# SCB_vongcochopet.net
KiCad netlist of a schematic drawn in Altium Designer
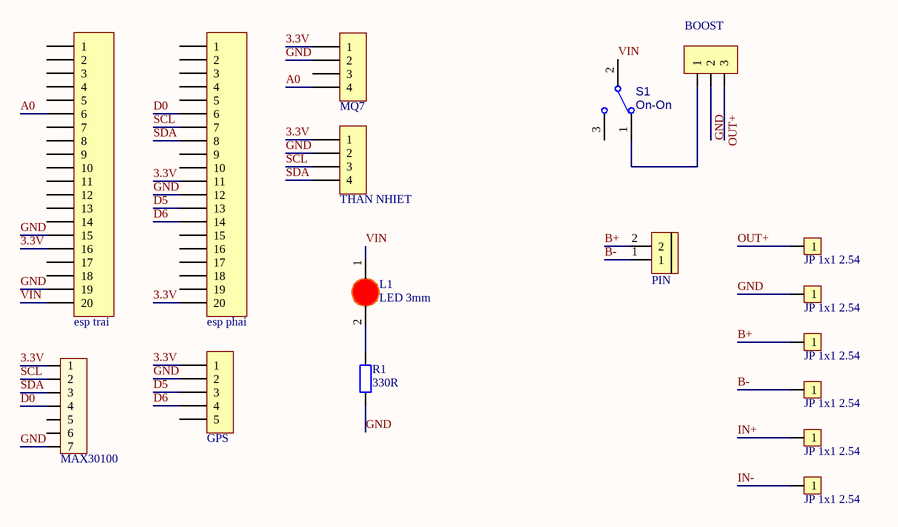
[diagram p0: SCB_vongcochopet.schdoc]

(export (version "E")
  (design (tool "Eeschema 10.0.6"))
  (components
    (comp (ref "H1")
      (value "MQ7")
      (footprint "Header DT 4P_2.54")
      (description "Cắm")
      (libsource (lib "Altium_Lib_by_KhueNguyenCreator") (part "Header 4P 2.54 Duc Thang"))
    )
    (comp (ref "H2")
      (value "THAN NHIET")
      (footprint "Header DT 4P_2.54")
      (description "Cắm")
      (libsource (lib "Altium_Lib_by_KhueNguyenCreator") (part "Header 4P 2.54 Duc Thang"))
    )
    (comp (ref "H3")
      (value "GPS")
      (footprint "Header DT 5P_2.54")
      (description "Cắm")
      (libsource (lib "Altium_Lib_by_KhueNguyenCreator") (part "Header 5P 2.54 Duc Thang"))
    )
    (comp (ref "H4")
      (value "MAX30100")
      (footprint "Header DT 7P_2.54")
      (description "Cắm")
      (libsource (lib "Altium_Lib_by_KhueNguyenCreator") (part "Header 7P 2.54 Duc Thang"))
    )
    (comp (ref "JP1")
      (value "esp trai")
      (footprint "JP 1x20 CT")
      (description "Cắm")
      (libsource (lib "Altium_Lib_by_KhueNguyenCreator") (part "JP 1x20 2.54 Cai Thang"))
    )
    (comp (ref "JP2")
      (value "esp phai")
      (footprint "JP 1x20 CT")
      (description "Cắm")
      (libsource (lib "Altium_Lib_by_KhueNguyenCreator") (part "JP 1x20 2.54 Cai Thang"))
    )
    (comp (ref "JP3")
      (value "BOOST")
      (footprint "JP 1x3 DT")
      (description "Cắm")
      (libsource (lib "Altium_Lib_by_KhueNguyenCreator") (part "JP 1x3 2.54 Duc Thang"))
    )
    (comp (ref "JP4")
      (value "JP 1x1 2.54")
      (footprint "JP 1x1 DT")
      (description "Cắm")
      (libsource (lib "Altium_Lib_by_KhueNguyenCreator") (part "JP 1x1 2.54 Duc Thang"))
    )
    (comp (ref "JP5")
      (value "JP 1x1 2.54")
      (footprint "JP 1x1 DT")
      (description "Cắm")
      (libsource (lib "Altium_Lib_by_KhueNguyenCreator") (part "JP 1x1 2.54 Duc Thang"))
    )
    (comp (ref "JP6")
      (value "JP 1x1 2.54")
      (footprint "JP 1x1 DT")
      (description "Cắm")
      (libsource (lib "Altium_Lib_by_KhueNguyenCreator") (part "JP 1x1 2.54 Duc Thang"))
    )
    (comp (ref "JP7")
      (value "JP 1x1 2.54")
      (footprint "JP 1x1 DT")
      (description "Cắm")
      (libsource (lib "Altium_Lib_by_KhueNguyenCreator") (part "JP 1x1 2.54 Duc Thang"))
    )
    (comp (ref "JP8")
      (value "JP 1x1 2.54")
      (footprint "JP 1x1 DT")
      (description "Cắm")
      (libsource (lib "Altium_Lib_by_KhueNguyenCreator") (part "JP 1x1 2.54 Duc Thang"))
    )
    (comp (ref "JP9")
      (value "JP 1x1 2.54")
      (footprint "JP 1x1 DT")
      (description "Cắm")
      (libsource (lib "Altium_Lib_by_KhueNguyenCreator") (part "JP 1x1 2.54 Duc Thang"))
    )
    (comp (ref "KF1")
      (value "PIN")
      (footprint "Con 2 KF301 5.08")
      (description "Cắm")
      (libsource (lib "Altium_Lib_by_KhueNguyenCreator") (part "CON 2 KF301"))
    )
    (comp (ref "L1")
      (value "LED 3mm")
      (footprint "LED-3MM-RED")
      (description "Cắm")
      (libsource (lib "Altium_Lib_by_KhueNguyenCreator") (part "LED 3mm Do"))
    )
    (comp (ref "R1")
      (value "330R")
      (footprint "tro vach 1/4w")
      (description "Cắm")
      (libsource (lib "Altium_Lib_by_KhueNguyenCreator") (part "Tro Vach 1/4W 5% 330R"))
    )
    (comp (ref "S1")
      (value "ON-ON")
      (footprint "SWITCH_SPDT_SLIDER")
      (description "Switch THD vertical toggle SPDT")
      (fields (field (name "SWITCH FUNCTION") "On-On"))
      (libsource (lib "My library altium") (part "SW_THD_SPDT_On-On"))
    )
  )
  (nets
    (net (code "1") (name "/3.3V") (class "Default")
      (node (ref "H1") (pin "1") (pinfunction "1_1") (pintype "passive"))
      (node (ref "H2") (pin "1") (pinfunction "1_1") (pintype "passive"))
      (node (ref "H3") (pin "1") (pinfunction "1_1") (pintype "passive"))
      (node (ref "H4") (pin "1") (pinfunction "1_1") (pintype "passive"))
      (node (ref "JP1") (pin "16") (pinfunction "16_16") (pintype "passive"))
      (node (ref "JP2") (pin "11") (pinfunction "11_11") (pintype "passive"))
      (node (ref "JP2") (pin "20") (pinfunction "20_20") (pintype "passive"))
    )
    (net (code "2") (name "/A0") (class "Default")
      (node (ref "H1") (pin "4") (pinfunction "4_4") (pintype "passive"))
      (node (ref "JP1") (pin "6") (pinfunction "6_6") (pintype "passive"))
    )
    (net (code "3") (name "/B+") (class "Default")
      (node (ref "JP6") (pin "1") (pinfunction "1_1") (pintype "passive"))
      (node (ref "KF1") (pin "2") (pinfunction "2_2") (pintype "passive"))
    )
    (net (code "4") (name "/B-") (class "Default")
      (node (ref "JP7") (pin "1") (pinfunction "1_1") (pintype "passive"))
      (node (ref "KF1") (pin "1") (pinfunction "1_1") (pintype "passive"))
    )
    (net (code "5") (name "/D0") (class "Default")
      (node (ref "H4") (pin "4") (pinfunction "4_4") (pintype "passive"))
      (node (ref "JP2") (pin "6") (pinfunction "6_6") (pintype "passive"))
    )
    (net (code "6") (name "/D5") (class "Default")
      (node (ref "H3") (pin "3") (pinfunction "3_3") (pintype "passive"))
      (node (ref "JP2") (pin "13") (pinfunction "13_13") (pintype "passive"))
    )
    (net (code "7") (name "/D6") (class "Default")
      (node (ref "H3") (pin "4") (pinfunction "4_4") (pintype "passive"))
      (node (ref "JP2") (pin "14") (pinfunction "14_14") (pintype "passive"))
    )
    (net (code "8") (name "/GND") (class "Default")
      (node (ref "H1") (pin "2") (pinfunction "2_2") (pintype "passive"))
      (node (ref "H2") (pin "2") (pinfunction "2_2") (pintype "passive"))
      (node (ref "H3") (pin "2") (pinfunction "2_2") (pintype "passive"))
      (node (ref "H4") (pin "7") (pinfunction "7_7") (pintype "passive"))
      (node (ref "JP1") (pin "15") (pinfunction "15_15") (pintype "passive"))
      (node (ref "JP1") (pin "19") (pinfunction "19_19") (pintype "passive"))
      (node (ref "JP2") (pin "12") (pinfunction "12_12") (pintype "passive"))
      (node (ref "JP3") (pin "2") (pinfunction "2_2") (pintype "passive"))
      (node (ref "JP5") (pin "1") (pinfunction "1_1") (pintype "passive"))
      (node (ref "R1") (pin "1") (pinfunction "1_1") (pintype "passive"))
    )
    (net (code "9") (name "/IN+") (class "Default")
      (node (ref "JP8") (pin "1") (pinfunction "1_1") (pintype "passive"))
    )
    (net (code "10") (name "/IN-") (class "Default")
      (node (ref "JP9") (pin "1") (pinfunction "1_1") (pintype "passive"))
    )
    (net (code "11") (name "/OUT+") (class "Default")
      (node (ref "JP3") (pin "3") (pinfunction "3_3") (pintype "passive"))
      (node (ref "JP4") (pin "1") (pinfunction "1_1") (pintype "passive"))
    )
    (net (code "12") (name "/SCL") (class "Default")
      (node (ref "H2") (pin "3") (pinfunction "3_3") (pintype "passive"))
      (node (ref "H4") (pin "2") (pinfunction "2_2") (pintype "passive"))
      (node (ref "JP2") (pin "7") (pinfunction "7_7") (pintype "passive"))
    )
    (net (code "13") (name "/SDA") (class "Default")
      (node (ref "H2") (pin "4") (pinfunction "4_4") (pintype "passive"))
      (node (ref "H4") (pin "3") (pinfunction "3_3") (pintype "passive"))
      (node (ref "JP2") (pin "8") (pinfunction "8_8") (pintype "passive"))
    )
    (net (code "14") (name "/VIN") (class "Default")
      (node (ref "JP1") (pin "20") (pinfunction "20_20") (pintype "passive"))
      (node (ref "L1") (pin "1") (pinfunction "A_1") (pintype "passive"))
      (node (ref "S1") (pin "2") (pinfunction "2_2") (pintype "passive"))
    )
    (net (code "15") (name "Net-(JP3-Pad1)") (class "Default")
      (node (ref "JP3") (pin "1") (pinfunction "1_1") (pintype "passive"))
      (node (ref "S1") (pin "1") (pinfunction "1_1") (pintype "passive"))
    )
    (net (code "16") (name "Net-(L1-K)") (class "Default")
      (node (ref "L1") (pin "2") (pinfunction "K_2") (pintype "passive"))
      (node (ref "R1") (pin "2") (pinfunction "2_2") (pintype "passive"))
    )
    (net (code "17") (name "unconnected-(H1-Pad3)") (class "Default")
      (node (ref "H1") (pin "3") (pinfunction "3_3") (pintype "passive"))
    )
    (net (code "18") (name "unconnected-(H3-Pad5)") (class "Default")
      (node (ref "H3") (pin "5") (pinfunction "5_5") (pintype "passive"))
    )
    (net (code "19") (name "unconnected-(H4-Pad5)") (class "Default")
      (node (ref "H4") (pin "5") (pinfunction "5_5") (pintype "passive"))
    )
    (net (code "20") (name "unconnected-(H4-Pad6)") (class "Default")
      (node (ref "H4") (pin "6") (pinfunction "6_6") (pintype "passive"))
    )
    (net (code "21") (name "unconnected-(JP1-Pad1)") (class "Default")
      (node (ref "JP1") (pin "1") (pinfunction "1_1") (pintype "passive"))
    )
    (net (code "22") (name "unconnected-(JP1-Pad2)") (class "Default")
      (node (ref "JP1") (pin "2") (pinfunction "2_2") (pintype "passive"))
    )
    (net (code "23") (name "unconnected-(JP1-Pad3)") (class "Default")
      (node (ref "JP1") (pin "3") (pinfunction "3_3") (pintype "passive"))
    )
    (net (code "24") (name "unconnected-(JP1-Pad4)") (class "Default")
      (node (ref "JP1") (pin "4") (pinfunction "4_4") (pintype "passive"))
    )
    (net (code "25") (name "unconnected-(JP1-Pad5)") (class "Default")
      (node (ref "JP1") (pin "5") (pinfunction "5_5") (pintype "passive"))
    )
    (net (code "26") (name "unconnected-(JP1-Pad7)") (class "Default")
      (node (ref "JP1") (pin "7") (pinfunction "7_7") (pintype "passive"))
    )
    (net (code "27") (name "unconnected-(JP1-Pad8)") (class "Default")
      (node (ref "JP1") (pin "8") (pinfunction "8_8") (pintype "passive"))
    )
    (net (code "28") (name "unconnected-(JP1-Pad9)") (class "Default")
      (node (ref "JP1") (pin "9") (pinfunction "9_9") (pintype "passive"))
    )
    (net (code "29") (name "unconnected-(JP1-Pad10)") (class "Default")
      (node (ref "JP1") (pin "10") (pinfunction "10_10") (pintype "passive"))
    )
    (net (code "30") (name "unconnected-(JP1-Pad11)") (class "Default")
      (node (ref "JP1") (pin "11") (pinfunction "11_11") (pintype "passive"))
    )
    (net (code "31") (name "unconnected-(JP1-Pad12)") (class "Default")
      (node (ref "JP1") (pin "12") (pinfunction "12_12") (pintype "passive"))
    )
    (net (code "32") (name "unconnected-(JP1-Pad13)") (class "Default")
      (node (ref "JP1") (pin "13") (pinfunction "13_13") (pintype "passive"))
    )
    (net (code "33") (name "unconnected-(JP1-Pad14)") (class "Default")
      (node (ref "JP1") (pin "14") (pinfunction "14_14") (pintype "passive"))
    )
    (net (code "34") (name "unconnected-(JP1-Pad17)") (class "Default")
      (node (ref "JP1") (pin "17") (pinfunction "17_17") (pintype "passive"))
    )
    (net (code "35") (name "unconnected-(JP1-Pad18)") (class "Default")
      (node (ref "JP1") (pin "18") (pinfunction "18_18") (pintype "passive"))
    )
    (net (code "36") (name "unconnected-(JP2-Pad1)") (class "Default")
      (node (ref "JP2") (pin "1") (pinfunction "1_1") (pintype "passive"))
    )
    (net (code "37") (name "unconnected-(JP2-Pad2)") (class "Default")
      (node (ref "JP2") (pin "2") (pinfunction "2_2") (pintype "passive"))
    )
    (net (code "38") (name "unconnected-(JP2-Pad3)") (class "Default")
      (node (ref "JP2") (pin "3") (pinfunction "3_3") (pintype "passive"))
    )
    (net (code "39") (name "unconnected-(JP2-Pad4)") (class "Default")
      (node (ref "JP2") (pin "4") (pinfunction "4_4") (pintype "passive"))
    )
    (net (code "40") (name "unconnected-(JP2-Pad5)") (class "Default")
      (node (ref "JP2") (pin "5") (pinfunction "5_5") (pintype "passive"))
    )
    (net (code "41") (name "unconnected-(JP2-Pad9)") (class "Default")
      (node (ref "JP2") (pin "9") (pinfunction "9_9") (pintype "passive"))
    )
    (net (code "42") (name "unconnected-(JP2-Pad10)") (class "Default")
      (node (ref "JP2") (pin "10") (pinfunction "10_10") (pintype "passive"))
    )
    (net (code "43") (name "unconnected-(JP2-Pad15)") (class "Default")
      (node (ref "JP2") (pin "15") (pinfunction "15_15") (pintype "passive"))
    )
    (net (code "44") (name "unconnected-(JP2-Pad16)") (class "Default")
      (node (ref "JP2") (pin "16") (pinfunction "16_16") (pintype "passive"))
    )
    (net (code "45") (name "unconnected-(JP2-Pad17)") (class "Default")
      (node (ref "JP2") (pin "17") (pinfunction "17_17") (pintype "passive"))
    )
    (net (code "46") (name "unconnected-(JP2-Pad18)") (class "Default")
      (node (ref "JP2") (pin "18") (pinfunction "18_18") (pintype "passive"))
    )
    (net (code "47") (name "unconnected-(JP2-Pad19)") (class "Default")
      (node (ref "JP2") (pin "19") (pinfunction "19_19") (pintype "passive"))
    )
    (net (code "48") (name "unconnected-(S1-Pad3)") (class "Default")
      (node (ref "S1") (pin "3") (pinfunction "3_3") (pintype "passive"))
    )
  )
)
